# Display.net
KiCad netlist of a schematic drawn in Altium Designer
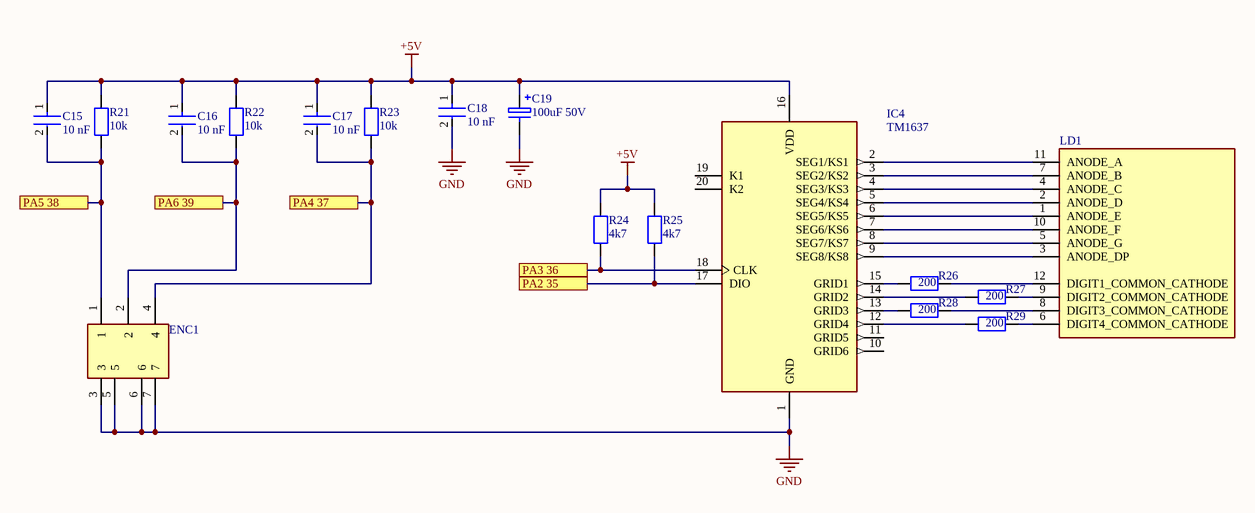
[diagram p0: Display.SchDoc]

(export (version "E")
  (design (tool "Eeschema 10.0.6"))
  (components
    (comp (ref "C15")
      (value "10 nF")
      (footprint "0805")
      (description "Chip Multilayer Ceramic Capacitors for General Purpose, 0805, 10uF, X5R, 15%, 10%, 25V")
      (fields (field (name "VOLTAGE") "25V") (field (name "TOLERANCE") "10%"))
      (libsource (lib "Schlib1") (part "Condensator 0805"))
    )
    (comp (ref "C16")
      (value "10 nF")
      (footprint "0805")
      (description "Chip Multilayer Ceramic Capacitors for General Purpose, 0805, 10uF, X5R, 15%, 10%, 25V")
      (fields (field (name "VOLTAGE") "25V") (field (name "TOLERANCE") "10%"))
      (libsource (lib "Schlib1") (part "Condensator 0805"))
    )
    (comp (ref "C17")
      (value "10 nF")
      (footprint "0805")
      (description "Chip Multilayer Ceramic Capacitors for General Purpose, 0805, 10uF, X5R, 15%, 10%, 25V")
      (fields (field (name "VOLTAGE") "25V") (field (name "TOLERANCE") "10%"))
      (libsource (lib "Schlib1") (part "Condensator 0805"))
    )
    (comp (ref "C18")
      (value "10 nF")
      (footprint "0805")
      (description "Chip Multilayer Ceramic Capacitors for General Purpose, 0805, 10uF, X5R, 15%, 10%, 25V")
      (fields (field (name "VOLTAGE") "25V") (field (name "TOLERANCE") "10%"))
      (libsource (lib "Schlib1") (part "Condensator 0805"))
    )
    (comp (ref "C19")
      (value "100uF 50V")
      (footprint "Elco 100uF 25V")
      (fields
        (field (name "PART NUMBER") "02015A270JAT2A")
        (field (name "MANUFACTURER") "AVX Interconnect / Elco")
      )
      (libsource (lib "Schlib1") (part "Condensator Elco"))
    )
    (comp (ref "ENC1")
      (value "PEC11R-4225F-S0024")
      (footprint "SamacSys:PEC12R-4XXXF-SXXXX_1")
      (description "Undefined or Miscellaneous")
      (fields (field (name "MOUSER2 PART NUMBER") "652-PEC11R-4225F-S24"))
      (libsource (lib "Schlib1") (part "Encoder"))
    )
    (comp (ref "IC4")
      (value "TM1637")
      (footprint "PcbLib1:TM1637")
      (description "LED Drive Control Special Circuit")
      (fields (field (name "MF") "Titan Micro Electronics"))
      (libsource (lib "Schlib1") (part "TM1637"))
    )
    (comp (ref "LD1")
      (value "HDSP-B09G")
      (footprint "PcbLib1:7 Segment Display")
      (fields (field (name "MF") "Broadcom Limited"))
      (libsource (lib "Schlib1") (part "7 Segment Display"))
    )
    (comp (ref "R21")
      (value "10k")
      (footprint "0805")
      (fields (field (name "MANUFACTURER") "Vishay Dale") (field (name "PART NUMBER") "CRCW08050000Z0EA"))
      (libsource (lib "Schlib1") (part "Resistor 0805"))
    )
    (comp (ref "R22")
      (value "10k")
      (footprint "0805")
      (fields (field (name "MANUFACTURER") "Vishay Dale") (field (name "PART NUMBER") "CRCW08050000Z0EA"))
      (libsource (lib "Schlib1") (part "Resistor 0805"))
    )
    (comp (ref "R23")
      (value "10k")
      (footprint "0805")
      (fields (field (name "MANUFACTURER") "Vishay Dale") (field (name "PART NUMBER") "CRCW08050000Z0EA"))
      (libsource (lib "Schlib1") (part "Resistor 0805"))
    )
    (comp (ref "R24")
      (value "4k7")
      (footprint "0805")
      (fields (field (name "MANUFACTURER") "Vishay Dale") (field (name "PART NUMBER") "CRCW08050000Z0EA"))
      (libsource (lib "Schlib1") (part "Resistor 0805"))
    )
    (comp (ref "R25")
      (value "4k7")
      (footprint "0805")
      (fields (field (name "MANUFACTURER") "Vishay Dale") (field (name "PART NUMBER") "CRCW08050000Z0EA"))
      (libsource (lib "Schlib1") (part "Resistor 0805"))
    )
    (comp (ref "R26")
      (value "200")
      (footprint "0805")
      (fields (field (name "MANUFACTURER") "Vishay Dale") (field (name "PART NUMBER") "CRCW08050000Z0EA"))
      (libsource (lib "Schlib1") (part "Resistor 0805"))
    )
    (comp (ref "R27")
      (value "200")
      (footprint "0805")
      (fields (field (name "MANUFACTURER") "Vishay Dale") (field (name "PART NUMBER") "CRCW08050000Z0EA"))
      (libsource (lib "Schlib1") (part "Resistor 0805"))
    )
    (comp (ref "R28")
      (value "200")
      (footprint "0805")
      (fields (field (name "MANUFACTURER") "Vishay Dale") (field (name "PART NUMBER") "CRCW08050000Z0EA"))
      (libsource (lib "Schlib1") (part "Resistor 0805"))
    )
    (comp (ref "R29")
      (value "200")
      (footprint "0805")
      (fields (field (name "MANUFACTURER") "Vishay Dale") (field (name "PART NUMBER") "CRCW08050000Z0EA"))
      (libsource (lib "Schlib1") (part "Resistor 0805"))
    )
  )
  (nets
    (net (code "1") (name "+5V") (class "Default")
      (node (ref "C15") (pin "1") (pinfunction "1_1") (pintype "passive"))
      (node (ref "C16") (pin "1") (pinfunction "1_1") (pintype "passive"))
      (node (ref "C17") (pin "1") (pinfunction "1_1") (pintype "passive"))
      (node (ref "C18") (pin "1") (pinfunction "1_1") (pintype "passive"))
      (node (ref "C19") (pin "1") (pinfunction "1_1") (pintype "passive"))
      (node (ref "IC4") (pin "16") (pinfunction "VDD_16") (pintype "power_in"))
      (node (ref "R21") (pin "1") (pinfunction "1_1") (pintype "passive"))
      (node (ref "R22") (pin "1") (pinfunction "1_1") (pintype "passive"))
      (node (ref "R23") (pin "1") (pinfunction "1_1") (pintype "passive"))
      (node (ref "R24") (pin "1") (pinfunction "1_1") (pintype "passive"))
      (node (ref "R25") (pin "1") (pinfunction "1_1") (pintype "passive"))
    )
    (net (code "2") (name "/PA2 35") (class "Default")
      (node (ref "IC4") (pin "17") (pinfunction "DIO_17") (pintype "passive"))
      (node (ref "R25") (pin "2") (pinfunction "2_2") (pintype "passive"))
    )
    (net (code "3") (name "/PA3 36") (class "Default")
      (node (ref "IC4") (pin "18") (pinfunction "CLK_18") (pintype "passive"))
      (node (ref "R24") (pin "2") (pinfunction "2_2") (pintype "passive"))
    )
    (net (code "4") (name "/PA4 37") (class "Default")
      (node (ref "C17") (pin "2") (pinfunction "2_2") (pintype "passive"))
      (node (ref "ENC1") (pin "4") (pinfunction "4_4") (pintype "passive"))
      (node (ref "R23") (pin "2") (pinfunction "2_2") (pintype "passive"))
    )
    (net (code "5") (name "/PA5 38") (class "Default")
      (node (ref "C15") (pin "2") (pinfunction "2_2") (pintype "passive"))
      (node (ref "ENC1") (pin "1") (pinfunction "1_1") (pintype "passive"))
      (node (ref "R21") (pin "2") (pinfunction "2_2") (pintype "passive"))
    )
    (net (code "6") (name "/PA6 39") (class "Default")
      (node (ref "C16") (pin "2") (pinfunction "2_2") (pintype "passive"))
      (node (ref "ENC1") (pin "2") (pinfunction "2_2") (pintype "passive"))
      (node (ref "R22") (pin "2") (pinfunction "2_2") (pintype "passive"))
    )
    (net (code "7") (name "GND") (class "Default")
      (node (ref "C18") (pin "2") (pinfunction "2_2") (pintype "passive"))
      (node (ref "C19") (pin "2") (pinfunction "2_2") (pintype "passive"))
      (node (ref "ENC1") (pin "3") (pinfunction "3_3") (pintype "passive"))
      (node (ref "ENC1") (pin "5") (pinfunction "5_5") (pintype "passive"))
      (node (ref "ENC1") (pin "6") (pinfunction "6_6") (pintype "passive"))
      (node (ref "ENC1") (pin "7") (pinfunction "7_7") (pintype "passive"))
      (node (ref "IC4") (pin "1") (pinfunction "GND_1") (pintype "power_in"))
    )
    (net (code "8") (name "Net-(IC4-GRID1)") (class "Default")
      (node (ref "IC4") (pin "15") (pinfunction "GRID1_15") (pintype "output"))
      (node (ref "R26") (pin "1") (pinfunction "1_1") (pintype "passive"))
    )
    (net (code "9") (name "Net-(IC4-GRID2)") (class "Default")
      (node (ref "IC4") (pin "14") (pinfunction "GRID2_14") (pintype "output"))
      (node (ref "R27") (pin "1") (pinfunction "1_1") (pintype "passive"))
    )
    (net (code "10") (name "Net-(IC4-GRID3)") (class "Default")
      (node (ref "IC4") (pin "13") (pinfunction "GRID3_13") (pintype "output"))
      (node (ref "R28") (pin "1") (pinfunction "1_1") (pintype "passive"))
    )
    (net (code "11") (name "Net-(IC4-GRID4)") (class "Default")
      (node (ref "IC4") (pin "12") (pinfunction "GRID4_12") (pintype "output"))
      (node (ref "R29") (pin "1") (pinfunction "1_1") (pintype "passive"))
    )
    (net (code "12") (name "Net-(IC4-SEG1{slash}KS1)") (class "Default")
      (node (ref "IC4") (pin "2") (pinfunction "SEG1/KS1_2") (pintype "output"))
      (node (ref "LD1") (pin "11") (pinfunction "ANODE_A_11") (pintype "passive"))
    )
    (net (code "13") (name "Net-(IC4-SEG2{slash}KS2)") (class "Default")
      (node (ref "IC4") (pin "3") (pinfunction "SEG2/KS2_3") (pintype "output"))
      (node (ref "LD1") (pin "7") (pinfunction "ANODE_B_7") (pintype "passive"))
    )
    (net (code "14") (name "Net-(IC4-SEG3{slash}KS3)") (class "Default")
      (node (ref "IC4") (pin "4") (pinfunction "SEG3/KS3_4") (pintype "output"))
      (node (ref "LD1") (pin "4") (pinfunction "ANODE_C_4") (pintype "passive"))
    )
    (net (code "15") (name "Net-(IC4-SEG4{slash}KS4)") (class "Default")
      (node (ref "IC4") (pin "5") (pinfunction "SEG4/KS4_5") (pintype "output"))
      (node (ref "LD1") (pin "2") (pinfunction "ANODE_D_2") (pintype "passive"))
    )
    (net (code "16") (name "Net-(IC4-SEG5{slash}KS5)") (class "Default")
      (node (ref "IC4") (pin "6") (pinfunction "SEG5/KS5_6") (pintype "output"))
      (node (ref "LD1") (pin "1") (pinfunction "ANODE_E_1") (pintype "passive"))
    )
    (net (code "17") (name "Net-(IC4-SEG6{slash}KS6)") (class "Default")
      (node (ref "IC4") (pin "7") (pinfunction "SEG6/KS6_7") (pintype "output"))
      (node (ref "LD1") (pin "10") (pinfunction "ANODE_F_10") (pintype "passive"))
    )
    (net (code "18") (name "Net-(IC4-SEG7{slash}KS7)") (class "Default")
      (node (ref "IC4") (pin "8") (pinfunction "SEG7/KS7_8") (pintype "output"))
      (node (ref "LD1") (pin "5") (pinfunction "ANODE_G_5") (pintype "passive"))
    )
    (net (code "19") (name "Net-(IC4-SEG8{slash}KS8)") (class "Default")
      (node (ref "IC4") (pin "9") (pinfunction "SEG8/KS8_9") (pintype "output"))
      (node (ref "LD1") (pin "3") (pinfunction "ANODE_DP_3") (pintype "passive"))
    )
    (net (code "20") (name "Net-(LD1-DIGIT1_COMMON_CATHODE)") (class "Default")
      (node (ref "LD1") (pin "12") (pinfunction "DIGIT1_COMMON_CATHODE_12") (pintype "passive"))
      (node (ref "R26") (pin "2") (pinfunction "2_2") (pintype "passive"))
    )
    (net (code "21") (name "Net-(LD1-DIGIT2_COMMON_CATHODE)") (class "Default")
      (node (ref "LD1") (pin "9") (pinfunction "DIGIT2_COMMON_CATHODE_9") (pintype "passive"))
      (node (ref "R27") (pin "2") (pinfunction "2_2") (pintype "passive"))
    )
    (net (code "22") (name "Net-(LD1-DIGIT3_COMMON_CATHODE)") (class "Default")
      (node (ref "LD1") (pin "8") (pinfunction "DIGIT3_COMMON_CATHODE_8") (pintype "passive"))
      (node (ref "R28") (pin "2") (pinfunction "2_2") (pintype "passive"))
    )
    (net (code "23") (name "Net-(LD1-DIGIT4_COMMON_CATHODE)") (class "Default")
      (node (ref "LD1") (pin "6") (pinfunction "DIGIT4_COMMON_CATHODE_6") (pintype "passive"))
      (node (ref "R29") (pin "2") (pinfunction "2_2") (pintype "passive"))
    )
    (net (code "24") (name "unconnected-(IC4-GRID5-Pad11)") (class "Default")
      (node (ref "IC4") (pin "11") (pinfunction "GRID5_11") (pintype "output"))
    )
    (net (code "25") (name "unconnected-(IC4-GRID6-Pad10)") (class "Default")
      (node (ref "IC4") (pin "10") (pinfunction "GRID6_10") (pintype "output"))
    )
    (net (code "26") (name "unconnected-(IC4-K1-Pad19)") (class "Default")
      (node (ref "IC4") (pin "19") (pinfunction "K1_19") (pintype "passive"))
    )
    (net (code "27") (name "unconnected-(IC4-K2-Pad20)") (class "Default")
      (node (ref "IC4") (pin "20") (pinfunction "K2_20") (pintype "passive"))
    )
  )
)
